# input_switch2.net
KiCad netlist of a schematic drawn in EAGLE
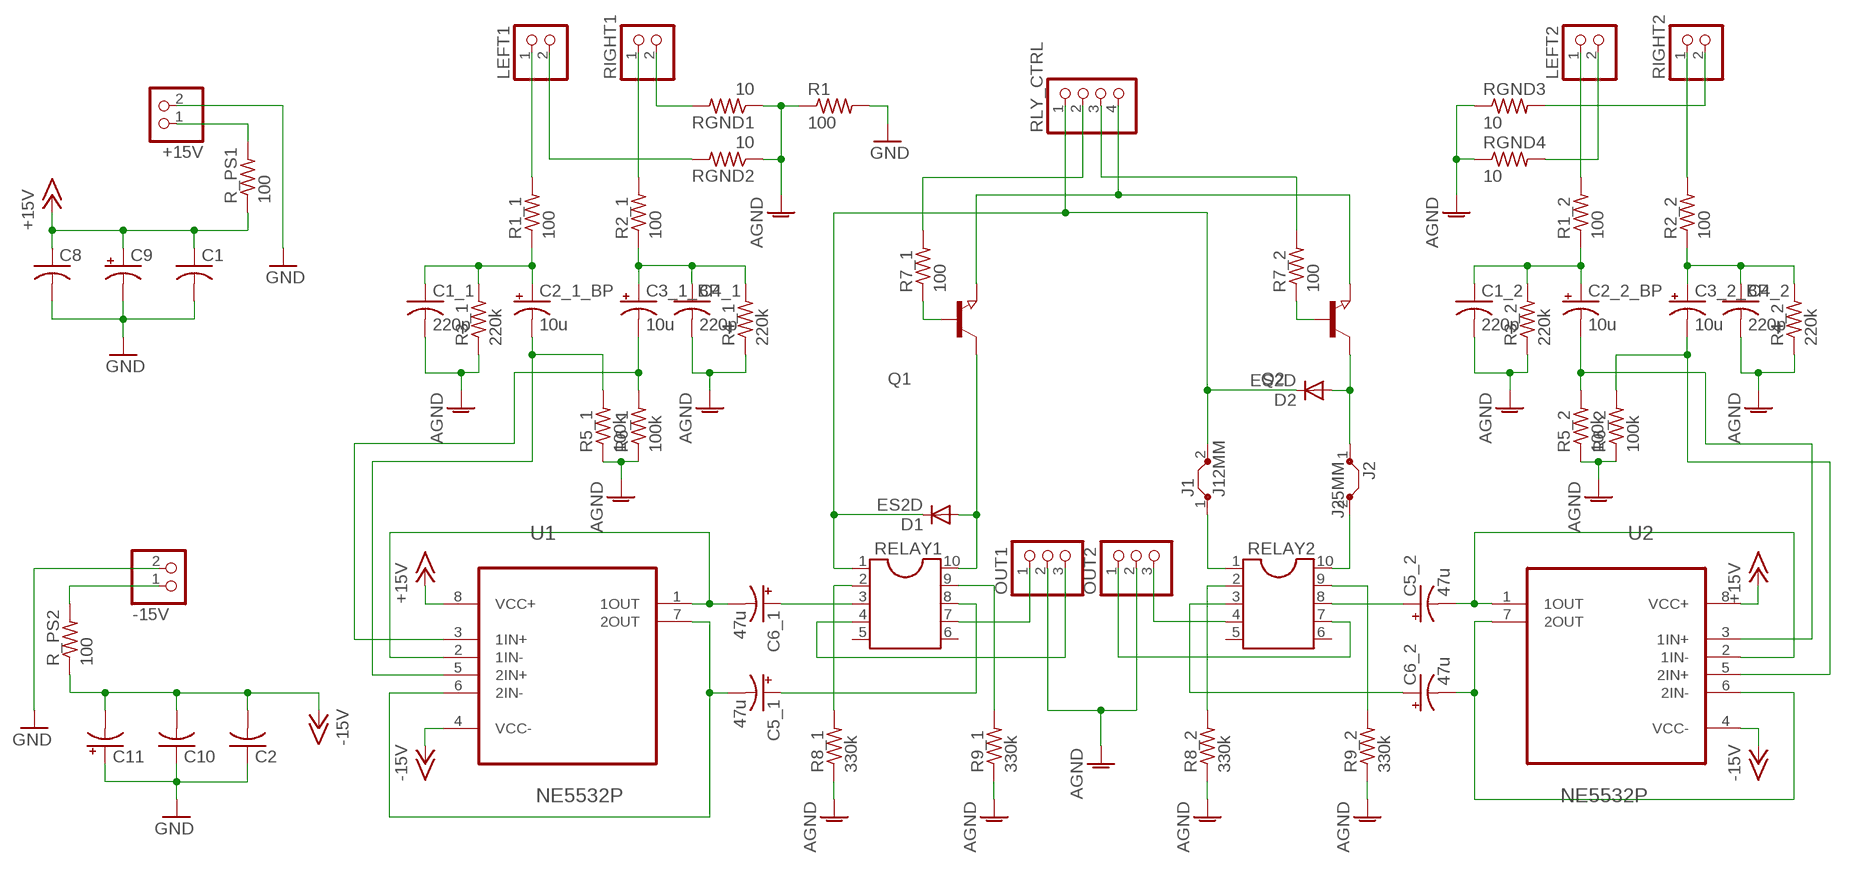
[diagram p0: schematic, sheet 1]

(export (version "E")
  (design (tool "Eeschema 10.0.6"))
  (components
    (comp (ref "+15V")
      (value "PINHD-1X2")
      (footprint "eagle-import:1X02")
      (libsource (lib "eagle-import") (part "PINHD-1X2"))
    )
    (comp (ref "-15V")
      (value "PINHD-1X2")
      (footprint "eagle-import:1X02")
      (libsource (lib "eagle-import") (part "PINHD-1X2"))
    )
    (comp (ref "C1")
      (value "C-USC1206")
      (footprint "eagle-import:C1206")
      (libsource (lib "eagle-import") (part "C-USC1206"))
    )
    (comp (ref "C1_1")
      (value "220p")
      (footprint "eagle-import:C025-024X044")
      (libsource (lib "eagle-import") (part "C-US025-024X044"))
    )
    (comp (ref "C1_2")
      (value "220p")
      (footprint "eagle-import:C025-024X044")
      (libsource (lib "eagle-import") (part "C-US025-024X044"))
    )
    (comp (ref "C2")
      (value "C-USC1206")
      (footprint "eagle-import:C1206")
      (libsource (lib "eagle-import") (part "C-USC1206"))
    )
    (comp (ref "C2_1_BP")
      (value "10u")
      (footprint "eagle-import:E2,5-7")
      (libsource (lib "eagle-import") (part "CPOL-USE2.5-7"))
    )
    (comp (ref "C2_2_BP")
      (value "10u")
      (footprint "eagle-import:E2,5-7")
      (libsource (lib "eagle-import") (part "CPOL-USE2.5-7"))
    )
    (comp (ref "C3_1_BP")
      (value "10u")
      (footprint "eagle-import:E2,5-7")
      (libsource (lib "eagle-import") (part "CPOL-USE2.5-7"))
    )
    (comp (ref "C3_2_BP")
      (value "10u")
      (footprint "eagle-import:E2,5-7")
      (libsource (lib "eagle-import") (part "CPOL-USE2.5-7"))
    )
    (comp (ref "C4_1")
      (value "220p")
      (footprint "eagle-import:C025-024X044")
      (libsource (lib "eagle-import") (part "C-US025-024X044"))
    )
    (comp (ref "C4_2")
      (value "220p")
      (footprint "eagle-import:C025-024X044")
      (libsource (lib "eagle-import") (part "C-US025-024X044"))
    )
    (comp (ref "C5_1")
      (value "47u")
      (footprint "eagle-import:E2-5")
      (libsource (lib "eagle-import") (part "CPOL-USE2-5"))
    )
    (comp (ref "C5_2")
      (value "47u")
      (footprint "eagle-import:E2-5")
      (libsource (lib "eagle-import") (part "CPOL-USE2-5"))
    )
    (comp (ref "C6_1")
      (value "47u")
      (footprint "eagle-import:E2-5")
      (libsource (lib "eagle-import") (part "CPOL-USE2-5"))
    )
    (comp (ref "C6_2")
      (value "47u")
      (footprint "eagle-import:E2-5")
      (libsource (lib "eagle-import") (part "CPOL-USE2-5"))
    )
    (comp (ref "C8")
      (value "C-USC1206")
      (footprint "eagle-import:C1206")
      (libsource (lib "eagle-import") (part "C-USC1206"))
    )
    (comp (ref "C9")
      (value "CPOL-USE2-5")
      (footprint "eagle-import:E2-5")
      (libsource (lib "eagle-import") (part "CPOL-USE2-5"))
    )
    (comp (ref "C10")
      (value "C-USC1206")
      (footprint "eagle-import:C1206")
      (libsource (lib "eagle-import") (part "C-USC1206"))
    )
    (comp (ref "C11")
      (value "CPOL-USE2-5")
      (footprint "eagle-import:E2-5")
      (libsource (lib "eagle-import") (part "CPOL-USE2-5"))
    )
    (comp (ref "D1")
      (value "ES2D")
      (footprint "eagle-import:SMB")
      (libsource (lib "eagle-import") (part "ES2D"))
    )
    (comp (ref "D2")
      (value "ES2D")
      (footprint "eagle-import:SMB")
      (libsource (lib "eagle-import") (part "ES2D"))
    )
    (comp (ref "J1")
      (value "J12MM")
      (footprint "eagle-import:12")
      (libsource (lib "eagle-import") (part "J12MM"))
    )
    (comp (ref "J2")
      (value "J25MM")
      (footprint "eagle-import:25")
      (libsource (lib "eagle-import") (part "J25MM"))
    )
    (comp (ref "LEFT1")
      (value "PINHD-1X2")
      (footprint "eagle-import:1X02")
      (libsource (lib "eagle-import") (part "PINHD-1X2"))
    )
    (comp (ref "LEFT2")
      (value "PINHD-1X2")
      (footprint "eagle-import:1X02")
      (libsource (lib "eagle-import") (part "PINHD-1X2"))
    )
    (comp (ref "OUT1")
      (value "PINHD-1X3")
      (footprint "eagle-import:1X03")
      (libsource (lib "eagle-import") (part "PINHD-1X3"))
    )
    (comp (ref "OUT2")
      (value "PINHD-1X3")
      (footprint "eagle-import:1X03")
      (libsource (lib "eagle-import") (part "PINHD-1X3"))
    )
    (comp (ref "Q1")
      (value "NPN-TRANSISTOR_SOT23")
      (footprint "eagle-import:SOT23")
      (libsource (lib "eagle-import") (part "NPN-TRANSISTOR_SOT23"))
    )
    (comp (ref "Q2")
      (value "NPN-TRANSISTOR_SOT23")
      (footprint "eagle-import:SOT23")
      (libsource (lib "eagle-import") (part "NPN-TRANSISTOR_SOT23"))
    )
    (comp (ref "R1")
      (value "100")
      (footprint "eagle-import:R1206")
      (libsource (lib "eagle-import") (part "R-US_R1206"))
    )
    (comp (ref "R1_1")
      (value "100")
      (footprint "eagle-import:0207_7")
      (libsource (lib "eagle-import") (part "R-US_0207/7"))
    )
    (comp (ref "R1_2")
      (value "100")
      (footprint "eagle-import:0207_7")
      (libsource (lib "eagle-import") (part "R-US_0207/7"))
    )
    (comp (ref "R2_1")
      (value "100")
      (footprint "eagle-import:0207_7")
      (libsource (lib "eagle-import") (part "R-US_0207/7"))
    )
    (comp (ref "R2_2")
      (value "100")
      (footprint "eagle-import:0207_7")
      (libsource (lib "eagle-import") (part "R-US_0207/7"))
    )
    (comp (ref "R3_1")
      (value "220k")
      (footprint "eagle-import:0207_7")
      (libsource (lib "eagle-import") (part "R-US_0207/7"))
    )
    (comp (ref "R3_2")
      (value "220k")
      (footprint "eagle-import:0207_7")
      (libsource (lib "eagle-import") (part "R-US_0207/7"))
    )
    (comp (ref "R4_1")
      (value "220k")
      (footprint "eagle-import:0207_7")
      (libsource (lib "eagle-import") (part "R-US_0207/7"))
    )
    (comp (ref "R4_2")
      (value "220k")
      (footprint "eagle-import:0207_7")
      (libsource (lib "eagle-import") (part "R-US_0207/7"))
    )
    (comp (ref "R5_1")
      (value "100k")
      (footprint "eagle-import:0207_7")
      (libsource (lib "eagle-import") (part "R-US_0207/7"))
    )
    (comp (ref "R5_2")
      (value "100k")
      (footprint "eagle-import:0207_7")
      (libsource (lib "eagle-import") (part "R-US_0207/7"))
    )
    (comp (ref "R6_1")
      (value "100k")
      (footprint "eagle-import:0207_7")
      (libsource (lib "eagle-import") (part "R-US_0207/7"))
    )
    (comp (ref "R6_2")
      (value "100k")
      (footprint "eagle-import:0207_7")
      (libsource (lib "eagle-import") (part "R-US_0207/7"))
    )
    (comp (ref "R7_1")
      (value "100")
      (footprint "eagle-import:R1206")
      (libsource (lib "eagle-import") (part "R-US_R1206"))
    )
    (comp (ref "R7_2")
      (value "100")
      (footprint "eagle-import:R1206")
      (libsource (lib "eagle-import") (part "R-US_R1206"))
    )
    (comp (ref "R8_1")
      (value "330k")
      (footprint "eagle-import:R1206")
      (libsource (lib "eagle-import") (part "R-US_R1206"))
    )
    (comp (ref "R8_2")
      (value "330k")
      (footprint "eagle-import:R1206")
      (libsource (lib "eagle-import") (part "R-US_R1206"))
    )
    (comp (ref "R9_1")
      (value "330k")
      (footprint "eagle-import:R1206")
      (libsource (lib "eagle-import") (part "R-US_R1206"))
    )
    (comp (ref "R9_2")
      (value "330k")
      (footprint "eagle-import:R1206")
      (libsource (lib "eagle-import") (part "R-US_R1206"))
    )
    (comp (ref "RELAY1")
      (value "DIL10")
      (footprint "eagle-import:DIL10")
      (libsource (lib "eagle-import") (part "DIL10"))
    )
    (comp (ref "RELAY2")
      (value "DIL10")
      (footprint "eagle-import:DIL10")
      (libsource (lib "eagle-import") (part "DIL10"))
    )
    (comp (ref "RGND1")
      (value "10")
      (footprint "eagle-import:R1206")
      (libsource (lib "eagle-import") (part "R-US_R1206"))
    )
    (comp (ref "RGND2")
      (value "10")
      (footprint "eagle-import:R1206")
      (libsource (lib "eagle-import") (part "R-US_R1206"))
    )
    (comp (ref "RGND3")
      (value "10")
      (footprint "eagle-import:R1206")
      (libsource (lib "eagle-import") (part "R-US_R1206"))
    )
    (comp (ref "RGND4")
      (value "10")
      (footprint "eagle-import:R1206")
      (libsource (lib "eagle-import") (part "R-US_R1206"))
    )
    (comp (ref "RIGHT1")
      (value "PINHD-1X2")
      (footprint "eagle-import:1X02")
      (libsource (lib "eagle-import") (part "PINHD-1X2"))
    )
    (comp (ref "RIGHT2")
      (value "PINHD-1X2")
      (footprint "eagle-import:1X02")
      (libsource (lib "eagle-import") (part "PINHD-1X2"))
    )
    (comp (ref "RLY_CTRL")
      (value "PINHD-1X4")
      (footprint "eagle-import:1X04")
      (libsource (lib "eagle-import") (part "PINHD-1X4"))
    )
    (comp (ref "R_PS1")
      (value "100")
      (footprint "eagle-import:0207_7")
      (libsource (lib "eagle-import") (part "R-US_0207/7"))
    )
    (comp (ref "R_PS2")
      (value "100")
      (footprint "eagle-import:0207_7")
      (libsource (lib "eagle-import") (part "R-US_0207/7"))
    )
    (comp (ref "U1")
      (value "NE5532P")
      (footprint "eagle-import:DIP254P762X508-8")
      (libsource (lib "eagle-import") (part "NE5532P"))
    )
    (comp (ref "U2")
      (value "NE5532P")
      (footprint "eagle-import:DIP254P762X508-8")
      (libsource (lib "eagle-import") (part "NE5532P"))
    )
  )
  (nets
    (net (code "1") (name "+15V") (class "Default")
      (node (ref "C1") (pin "1") (pinfunction "1_1") (pintype "passive"))
      (node (ref "C8") (pin "1") (pinfunction "1_1") (pintype "passive"))
      (node (ref "C9") (pin "+") (pinfunction "+_+") (pintype "passive"))
      (node (ref "R_PS1") (pin "1") (pinfunction "1_1") (pintype "passive"))
      (node (ref "U1") (pin "8") (pinfunction "VCC+_8") (pintype "power_in"))
      (node (ref "U2") (pin "8") (pinfunction "VCC+_8") (pintype "power_in"))
    )
    (net (code "2") (name "-15V") (class "Default")
      (node (ref "C10") (pin "2") (pinfunction "2_2") (pintype "passive"))
      (node (ref "C11") (pin "-") (pinfunction "-_-") (pintype "passive"))
      (node (ref "C2") (pin "2") (pinfunction "2_2") (pintype "passive"))
      (node (ref "R_PS2") (pin "1") (pinfunction "1_1") (pintype "passive"))
      (node (ref "U1") (pin "4") (pinfunction "VCC-_4") (pintype "power_in"))
      (node (ref "U2") (pin "4") (pinfunction "VCC-_4") (pintype "power_in"))
    )
    (net (code "3") (name "AGND") (class "Default")
      (node (ref "C1_1") (pin "2") (pinfunction "2_2") (pintype "passive"))
      (node (ref "C1_2") (pin "2") (pinfunction "2_2") (pintype "passive"))
      (node (ref "C4_1") (pin "2") (pinfunction "2_2") (pintype "passive"))
      (node (ref "C4_2") (pin "2") (pinfunction "2_2") (pintype "passive"))
      (node (ref "OUT1") (pin "2") (pinfunction "2_2") (pintype "passive"))
      (node (ref "OUT2") (pin "2") (pinfunction "2_2") (pintype "passive"))
      (node (ref "R1") (pin "1") (pinfunction "1_1") (pintype "passive"))
      (node (ref "R3_1") (pin "1") (pinfunction "1_1") (pintype "passive"))
      (node (ref "R3_2") (pin "1") (pinfunction "1_1") (pintype "passive"))
      (node (ref "R4_1") (pin "1") (pinfunction "1_1") (pintype "passive"))
      (node (ref "R4_2") (pin "1") (pinfunction "1_1") (pintype "passive"))
      (node (ref "R5_1") (pin "1") (pinfunction "1_1") (pintype "passive"))
      (node (ref "R5_2") (pin "1") (pinfunction "1_1") (pintype "passive"))
      (node (ref "R6_1") (pin "1") (pinfunction "1_1") (pintype "passive"))
      (node (ref "R6_2") (pin "1") (pinfunction "1_1") (pintype "passive"))
      (node (ref "R8_1") (pin "1") (pinfunction "1_1") (pintype "passive"))
      (node (ref "R8_2") (pin "1") (pinfunction "1_1") (pintype "passive"))
      (node (ref "R9_1") (pin "1") (pinfunction "1_1") (pintype "passive"))
      (node (ref "R9_2") (pin "1") (pinfunction "1_1") (pintype "passive"))
      (node (ref "RGND1") (pin "1") (pinfunction "1_1") (pintype "passive"))
      (node (ref "RGND2") (pin "1") (pinfunction "1_1") (pintype "passive"))
      (node (ref "RGND3") (pin "1") (pinfunction "1_1") (pintype "passive"))
      (node (ref "RGND4") (pin "1") (pinfunction "1_1") (pintype "passive"))
    )
    (net (code "4") (name "GND") (class "Default")
      (node (ref "+15V") (pin "2") (pinfunction "2_2") (pintype "passive"))
      (node (ref "-15V") (pin "2") (pinfunction "2_2") (pintype "passive"))
      (node (ref "C1") (pin "2") (pinfunction "2_2") (pintype "passive"))
      (node (ref "C10") (pin "1") (pinfunction "1_1") (pintype "passive"))
      (node (ref "C11") (pin "+") (pinfunction "+_+") (pintype "passive"))
      (node (ref "C2") (pin "1") (pinfunction "1_1") (pintype "passive"))
      (node (ref "C8") (pin "2") (pinfunction "2_2") (pintype "passive"))
      (node (ref "C9") (pin "-") (pinfunction "-_-") (pintype "passive"))
      (node (ref "R1") (pin "2") (pinfunction "2_2") (pintype "passive"))
    )
    (net (code "5") (name "Net-(+15V-Pad1)") (class "Default")
      (node (ref "+15V") (pin "1") (pinfunction "1_1") (pintype "passive"))
      (node (ref "R_PS1") (pin "2") (pinfunction "2_2") (pintype "passive"))
    )
    (net (code "6") (name "Net-(-15V-Pad1)") (class "Default")
      (node (ref "-15V") (pin "1") (pinfunction "1_1") (pintype "passive"))
      (node (ref "R_PS2") (pin "2") (pinfunction "2_2") (pintype "passive"))
    )
    (net (code "7") (name "Net-(C1_1-Pad1)") (class "Default")
      (node (ref "C1_1") (pin "1") (pinfunction "1_1") (pintype "passive"))
      (node (ref "C2_1_BP") (pin "+") (pinfunction "+_+") (pintype "passive"))
      (node (ref "R1_1") (pin "1") (pinfunction "1_1") (pintype "passive"))
      (node (ref "R3_1") (pin "2") (pinfunction "2_2") (pintype "passive"))
    )
    (net (code "8") (name "Net-(C1_2-Pad1)") (class "Default")
      (node (ref "C1_2") (pin "1") (pinfunction "1_1") (pintype "passive"))
      (node (ref "C2_2_BP") (pin "+") (pinfunction "+_+") (pintype "passive"))
      (node (ref "R1_2") (pin "1") (pinfunction "1_1") (pintype "passive"))
      (node (ref "R3_2") (pin "2") (pinfunction "2_2") (pintype "passive"))
    )
    (net (code "9") (name "Net-(C3_1_BP-Pad+)") (class "Default")
      (node (ref "C3_1_BP") (pin "+") (pinfunction "+_+") (pintype "passive"))
      (node (ref "C4_1") (pin "1") (pinfunction "1_1") (pintype "passive"))
      (node (ref "R2_1") (pin "1") (pinfunction "1_1") (pintype "passive"))
      (node (ref "R4_1") (pin "2") (pinfunction "2_2") (pintype "passive"))
    )
    (net (code "10") (name "Net-(C3_2_BP-Pad+)") (class "Default")
      (node (ref "C3_2_BP") (pin "+") (pinfunction "+_+") (pintype "passive"))
      (node (ref "C4_2") (pin "1") (pinfunction "1_1") (pintype "passive"))
      (node (ref "R2_2") (pin "1") (pinfunction "1_1") (pintype "passive"))
      (node (ref "R4_2") (pin "2") (pinfunction "2_2") (pintype "passive"))
    )
    (net (code "11") (name "Net-(C5_1-Pad+)") (class "Default")
      (node (ref "C5_1") (pin "+") (pinfunction "+_+") (pintype "passive"))
      (node (ref "RELAY1") (pin "8") (pinfunction "8_8") (pintype "passive"))
    )
    (net (code "12") (name "Net-(C5_2-Pad+)") (class "Default")
      (node (ref "C5_2") (pin "+") (pinfunction "+_+") (pintype "passive"))
      (node (ref "RELAY2") (pin "8") (pinfunction "8_8") (pintype "passive"))
    )
    (net (code "13") (name "Net-(C6_1-Pad+)") (class "Default")
      (node (ref "C6_1") (pin "+") (pinfunction "+_+") (pintype "passive"))
      (node (ref "RELAY1") (pin "3") (pinfunction "3_3") (pintype "passive"))
    )
    (net (code "14") (name "Net-(C6_2-Pad+)") (class "Default")
      (node (ref "C6_2") (pin "+") (pinfunction "+_+") (pintype "passive"))
      (node (ref "RELAY2") (pin "3") (pinfunction "3_3") (pintype "passive"))
    )
    (net (code "15") (name "Net-(D1-PadC)") (class "Default")
      (node (ref "D1") (pin "C") (pinfunction "C_C") (pintype "passive"))
      (node (ref "D2") (pin "C") (pinfunction "C_C") (pintype "passive"))
      (node (ref "J1") (pin "2") (pinfunction "2_2") (pintype "passive"))
      (node (ref "RELAY1") (pin "1") (pinfunction "1_1") (pintype "passive"))
      (node (ref "RLY_CTRL") (pin "1") (pinfunction "1_1") (pintype "passive"))
    )
    (net (code "16") (name "Net-(J1-Pad1)") (class "Default")
      (node (ref "J1") (pin "1") (pinfunction "1_1") (pintype "passive"))
      (node (ref "RELAY2") (pin "1") (pinfunction "1_1") (pintype "passive"))
    )
    (net (code "17") (name "Net-(J2-Pad2)") (class "Default")
      (node (ref "J2") (pin "2") (pinfunction "2_2") (pintype "passive"))
      (node (ref "RELAY2") (pin "10") (pinfunction "10_10") (pintype "passive"))
    )
    (net (code "18") (name "Net-(LEFT1-Pad1)") (class "Default")
      (node (ref "LEFT1") (pin "1") (pinfunction "1_1") (pintype "passive"))
      (node (ref "R1_1") (pin "2") (pinfunction "2_2") (pintype "passive"))
    )
    (net (code "19") (name "Net-(LEFT1-Pad2)") (class "Default")
      (node (ref "LEFT1") (pin "2") (pinfunction "2_2") (pintype "passive"))
      (node (ref "RGND2") (pin "2") (pinfunction "2_2") (pintype "passive"))
    )
    (net (code "20") (name "Net-(LEFT2-Pad1)") (class "Default")
      (node (ref "LEFT2") (pin "1") (pinfunction "1_1") (pintype "passive"))
      (node (ref "R1_2") (pin "2") (pinfunction "2_2") (pintype "passive"))
    )
    (net (code "21") (name "Net-(LEFT2-Pad2)") (class "Default")
      (node (ref "LEFT2") (pin "2") (pinfunction "2_2") (pintype "passive"))
      (node (ref "RGND4") (pin "2") (pinfunction "2_2") (pintype "passive"))
    )
    (net (code "22") (name "Net-(OUT1-Pad1)") (class "Default")
      (node (ref "OUT1") (pin "1") (pinfunction "1_1") (pintype "passive"))
      (node (ref "RELAY1") (pin "7") (pinfunction "7_7") (pintype "passive"))
    )
    (net (code "23") (name "Net-(OUT1-Pad3)") (class "Default")
      (node (ref "OUT1") (pin "3") (pinfunction "3_3") (pintype "passive"))
      (node (ref "RELAY1") (pin "4") (pinfunction "4_4") (pintype "passive"))
    )
    (net (code "24") (name "Net-(OUT2-Pad1)") (class "Default")
      (node (ref "OUT2") (pin "1") (pinfunction "1_1") (pintype "passive"))
      (node (ref "RELAY2") (pin "7") (pinfunction "7_7") (pintype "passive"))
    )
    (net (code "25") (name "Net-(OUT2-Pad3)") (class "Default")
      (node (ref "OUT2") (pin "3") (pinfunction "3_3") (pintype "passive"))
      (node (ref "RELAY2") (pin "4") (pinfunction "4_4") (pintype "passive"))
    )
    (net (code "26") (name "Net-(Q1-B)") (class "Default")
      (node (ref "Q1") (pin "1") (pinfunction "B_1") (pintype "passive"))
      (node (ref "R7_1") (pin "1") (pinfunction "1_1") (pintype "passive"))
    )
    (net (code "27") (name "Net-(Q1-C)") (class "Default")
      (node (ref "D1") (pin "A") (pinfunction "A_A") (pintype "passive"))
      (node (ref "Q1") (pin "3") (pinfunction "C_3") (pintype "passive"))
      (node (ref "RELAY1") (pin "10") (pinfunction "10_10") (pintype "passive"))
    )
    (net (code "28") (name "Net-(Q1-E)") (class "Default")
      (node (ref "Q1") (pin "2") (pinfunction "E_2") (pintype "passive"))
      (node (ref "Q2") (pin "2") (pinfunction "E_2") (pintype "passive"))
      (node (ref "RLY_CTRL") (pin "4") (pinfunction "4_4") (pintype "passive"))
    )
    (net (code "29") (name "Net-(Q2-B)") (class "Default")
      (node (ref "Q2") (pin "1") (pinfunction "B_1") (pintype "passive"))
      (node (ref "R7_2") (pin "1") (pinfunction "1_1") (pintype "passive"))
    )
    (net (code "30") (name "Net-(Q2-C)") (class "Default")
      (node (ref "D2") (pin "A") (pinfunction "A_A") (pintype "passive"))
      (node (ref "J2") (pin "1") (pinfunction "1_1") (pintype "passive"))
      (node (ref "Q2") (pin "3") (pinfunction "C_3") (pintype "passive"))
    )
    (net (code "31") (name "Net-(R2_1-Pad2)") (class "Default")
      (node (ref "R2_1") (pin "2") (pinfunction "2_2") (pintype "passive"))
      (node (ref "RIGHT1") (pin "1") (pinfunction "1_1") (pintype "passive"))
    )
    (net (code "32") (name "Net-(R2_2-Pad2)") (class "Default")
      (node (ref "R2_2") (pin "2") (pinfunction "2_2") (pintype "passive"))
      (node (ref "RIGHT2") (pin "1") (pinfunction "1_1") (pintype "passive"))
    )
    (net (code "33") (name "Net-(R7_1-Pad2)") (class "Default")
      (node (ref "R7_1") (pin "2") (pinfunction "2_2") (pintype "passive"))
      (node (ref "RLY_CTRL") (pin "2") (pinfunction "2_2") (pintype "passive"))
    )
    (net (code "34") (name "Net-(R7_2-Pad2)") (class "Default")
      (node (ref "R7_2") (pin "2") (pinfunction "2_2") (pintype "passive"))
      (node (ref "RLY_CTRL") (pin "3") (pinfunction "3_3") (pintype "passive"))
    )
    (net (code "35") (name "Net-(R8_1-Pad2)") (class "Default")
      (node (ref "R8_1") (pin "2") (pinfunction "2_2") (pintype "passive"))
      (node (ref "RELAY1") (pin "2") (pinfunction "2_2") (pintype "passive"))
    )
    (net (code "36") (name "Net-(R8_2-Pad2)") (class "Default")
      (node (ref "R8_2") (pin "2") (pinfunction "2_2") (pintype "passive"))
      (node (ref "RELAY2") (pin "2") (pinfunction "2_2") (pintype "passive"))
    )
    (net (code "37") (name "Net-(R9_1-Pad2)") (class "Default")
      (node (ref "R9_1") (pin "2") (pinfunction "2_2") (pintype "passive"))
      (node (ref "RELAY1") (pin "9") (pinfunction "9_9") (pintype "passive"))
    )
    (net (code "38") (name "Net-(R9_2-Pad2)") (class "Default")
      (node (ref "R9_2") (pin "2") (pinfunction "2_2") (pintype "passive"))
      (node (ref "RELAY2") (pin "9") (pinfunction "9_9") (pintype "passive"))
    )
    (net (code "39") (name "Net-(RGND1-Pad2)") (class "Default")
      (node (ref "RGND1") (pin "2") (pinfunction "2_2") (pintype "passive"))
      (node (ref "RIGHT1") (pin "2") (pinfunction "2_2") (pintype "passive"))
    )
    (net (code "40") (name "Net-(RGND3-Pad2)") (class "Default")
      (node (ref "RGND3") (pin "2") (pinfunction "2_2") (pintype "passive"))
      (node (ref "RIGHT2") (pin "2") (pinfunction "2_2") (pintype "passive"))
    )
    (net (code "41") (name "Net-(U1-1IN+)") (class "Default")
      (node (ref "C3_1_BP") (pin "-") (pinfunction "-_-") (pintype "passive"))
      (node (ref "R6_1") (pin "2") (pinfunction "2_2") (pintype "passive"))
      (node (ref "U1") (pin "3") (pinfunction "1IN+_3") (pintype "input"))
    )
    (net (code "42") (name "Net-(U1-1IN-)") (class "Default")
      (node (ref "C6_1") (pin "-") (pinfunction "-_-") (pintype "passive"))
      (node (ref "U1") (pin "1") (pinfunction "1OUT_1") (pintype "output"))
      (node (ref "U1") (pin "2") (pinfunction "1IN-_2") (pintype "input"))
    )
    (net (code "43") (name "Net-(U1-2IN+)") (class "Default")
      (node (ref "C2_1_BP") (pin "-") (pinfunction "-_-") (pintype "passive"))
      (node (ref "R5_1") (pin "2") (pinfunction "2_2") (pintype "passive"))
      (node (ref "U1") (pin "5") (pinfunction "2IN+_5") (pintype "input"))
    )
    (net (code "44") (name "Net-(U1-2IN-)") (class "Default")
      (node (ref "C5_1") (pin "-") (pinfunction "-_-") (pintype "passive"))
      (node (ref "U1") (pin "6") (pinfunction "2IN-_6") (pintype "input"))
      (node (ref "U1") (pin "7") (pinfunction "2OUT_7") (pintype "output"))
    )
    (net (code "45") (name "Net-(U2-1IN+)") (class "Default")
      (node (ref "C2_2_BP") (pin "-") (pinfunction "-_-") (pintype "passive"))
      (node (ref "R5_2") (pin "2") (pinfunction "2_2") (pintype "passive"))
      (node (ref "U2") (pin "3") (pinfunction "1IN+_3") (pintype "input"))
    )
    (net (code "46") (name "Net-(U2-1IN-)") (class "Default")
      (node (ref "C5_2") (pin "-") (pinfunction "-_-") (pintype "passive"))
      (node (ref "U2") (pin "1") (pinfunction "1OUT_1") (pintype "output"))
      (node (ref "U2") (pin "2") (pinfunction "1IN-_2") (pintype "input"))
    )
    (net (code "47") (name "Net-(U2-2IN+)") (class "Default")
      (node (ref "C3_2_BP") (pin "-") (pinfunction "-_-") (pintype "passive"))
      (node (ref "R6_2") (pin "2") (pinfunction "2_2") (pintype "passive"))
      (node (ref "U2") (pin "5") (pinfunction "2IN+_5") (pintype "input"))
    )
    (net (code "48") (name "Net-(U2-2IN-)") (class "Default")
      (node (ref "C6_2") (pin "-") (pinfunction "-_-") (pintype "passive"))
      (node (ref "U2") (pin "6") (pinfunction "2IN-_6") (pintype "input"))
      (node (ref "U2") (pin "7") (pinfunction "2OUT_7") (pintype "output"))
    )
    (net (code "49") (name "unconnected-(RELAY1-Pad5)") (class "Default")
      (node (ref "RELAY1") (pin "5") (pinfunction "5_5") (pintype "passive"))
    )
    (net (code "50") (name "unconnected-(RELAY1-Pad6)") (class "Default")
      (node (ref "RELAY1") (pin "6") (pinfunction "6_6") (pintype "passive"))
    )
    (net (code "51") (name "unconnected-(RELAY2-Pad5)") (class "Default")
      (node (ref "RELAY2") (pin "5") (pinfunction "5_5") (pintype "passive"))
    )
    (net (code "52") (name "unconnected-(RELAY2-Pad6)") (class "Default")
      (node (ref "RELAY2") (pin "6") (pinfunction "6_6") (pintype "passive"))
    )
  )
)
